# 5_-MCU_CONNECTORS.net
KiCad netlist of a schematic drawn in Altium Designer
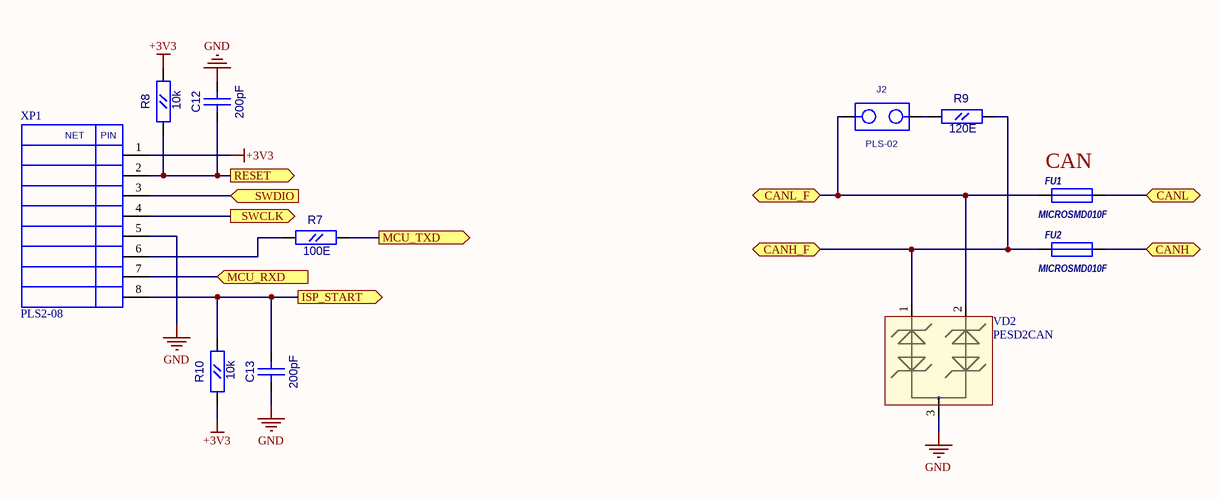
[diagram p0: [5]-MCU_CONNECTORS.SchDoc]

(export (version "E")
  (design (tool "Eeschema 10.0.6"))
  (components
    (comp (ref "C12")
      (value "200pF")
      (footprint "CC0603")
      (description "CC0603")
      (libsource (lib "gprs_modem_2") (part "CC0603"))
    )
    (comp (ref "C13")
      (value "200pF")
      (footprint "CC0603")
      (description "CC0603")
      (libsource (lib "gprs_modem_2") (part "CC0603"))
    )
    (comp (ref "FU1")
      (value "MICROSMD010F")
      (footprint "RC1210")
      (description "MICROSMD")
      (libsource (lib "gprs_modem_2") (part "MICROSMD"))
    )
    (comp (ref "FU2")
      (value "MICROSMD010F")
      (footprint "RC1210")
      (description "MICROSMD")
      (libsource (lib "gprs_modem_2") (part "MICROSMD"))
    )
    (comp (ref "J2") (value "PLS-02") (footprint "PLS-02") (libsource (lib "fizik_lib") (part "PLS-02")))
    (comp (ref "R7")
      (value "100E")
      (footprint "RC0603")
      (description "RC0603")
      (libsource (lib "gprs_modem_2") (part "RC0603"))
    )
    (comp (ref "R8")
      (value "10k")
      (footprint "RC0603")
      (description "RC0603")
      (libsource (lib "gprs_modem_2") (part "RC0603"))
    )
    (comp (ref "R9")
      (value "120E")
      (footprint "RC0805")
      (description "RC0805")
      (libsource (lib "fizik_lib") (part "RC0805"))
    )
    (comp (ref "R10")
      (value "10k")
      (footprint "RC0603")
      (description "RC0603")
      (libsource (lib "gprs_modem_2") (part "RC0603"))
    )
    (comp (ref "VD2")
      (value "PESD2CAN")
      (footprint "SOT-23(123)")
      (description "TVS for CAN")
      (libsource (lib "gprs_modem_2") (part "PESD2CAN"))
    )
    (comp (ref "XP1") (value "PLS2-08") (footprint "PLS2-08") (libsource (lib "fizik_lib") (part "PLS2-08")))
  )
  (nets
    (net (code "1") (name "+3V3") (class "Default")
      (node (ref "R10") (pin "1") (pinfunction "A_1") (pintype "passive"))
      (node (ref "R8") (pin "2") (pinfunction "B_2") (pintype "passive"))
      (node (ref "XP1") (pin "1") (pinfunction "1_1") (pintype "passive"))
    )
    (net (code "2") (name "/CANH") (class "Default") (node (ref "FU2") (pin "2") (pintype "passive")))
    (net (code "3") (name "/CANH_F") (class "Default")
      (node (ref "FU2") (pin "1") (pintype "passive"))
      (node (ref "R9") (pin "2") (pinfunction "B_2") (pintype "passive"))
      (node (ref "VD2") (pin "1") (pinfunction "1_1") (pintype "passive"))
    )
    (net (code "4") (name "/CANL") (class "Default") (node (ref "FU1") (pin "2") (pintype "passive")))
    (net (code "5") (name "/CANL_F") (class "Default")
      (node (ref "FU1") (pin "1") (pintype "passive"))
      (node (ref "J2") (pin "1") (pintype "passive"))
      (node (ref "VD2") (pin "2") (pinfunction "2_2") (pintype "passive"))
    )
    (net (code "6") (name "/ISP_START") (class "Default")
      (node (ref "C13") (pin "2") (pinfunction "B_2") (pintype "passive"))
      (node (ref "R10") (pin "2") (pinfunction "B_2") (pintype "passive"))
      (node (ref "XP1") (pin "8") (pinfunction "8_8") (pintype "passive"))
    )
    (net (code "7") (name "/MCU_RXD") (class "Default")
      (node (ref "XP1") (pin "7") (pinfunction "7_7") (pintype "passive"))
    )
    (net (code "8") (name "/MCU_TXD") (class "Default")
      (node (ref "R7") (pin "2") (pinfunction "B_2") (pintype "passive"))
    )
    (net (code "9") (name "/RESET") (class "Default")
      (node (ref "C12") (pin "1") (pinfunction "A_1") (pintype "passive"))
      (node (ref "R8") (pin "1") (pinfunction "A_1") (pintype "passive"))
      (node (ref "XP1") (pin "2") (pinfunction "2_2") (pintype "passive"))
    )
    (net (code "10") (name "/SWCLK") (class "Default")
      (node (ref "XP1") (pin "4") (pinfunction "4_4") (pintype "passive"))
    )
    (net (code "11") (name "/SWDIO") (class "Default")
      (node (ref "XP1") (pin "3") (pinfunction "3_3") (pintype "passive"))
    )
    (net (code "12") (name "GND") (class "Default")
      (node (ref "C12") (pin "2") (pinfunction "B_2") (pintype "passive"))
      (node (ref "C13") (pin "1") (pinfunction "A_1") (pintype "passive"))
      (node (ref "VD2") (pin "3") (pinfunction "3_3") (pintype "passive"))
      (node (ref "XP1") (pin "5") (pinfunction "5_5") (pintype "passive"))
    )
    (net (code "13") (name "Net-(R7-A)") (class "Default")
      (node (ref "R7") (pin "1") (pinfunction "A_1") (pintype "passive"))
      (node (ref "XP1") (pin "6") (pinfunction "6_6") (pintype "passive"))
    )
    (net (code "14") (name "Net-(R9-A)") (class "Default")
      (node (ref "J2") (pin "2") (pintype "passive"))
      (node (ref "R9") (pin "1") (pinfunction "A_1") (pintype "passive"))
    )
  )
)
